# MCU.net
KiCad netlist of a schematic drawn in Altium Designer
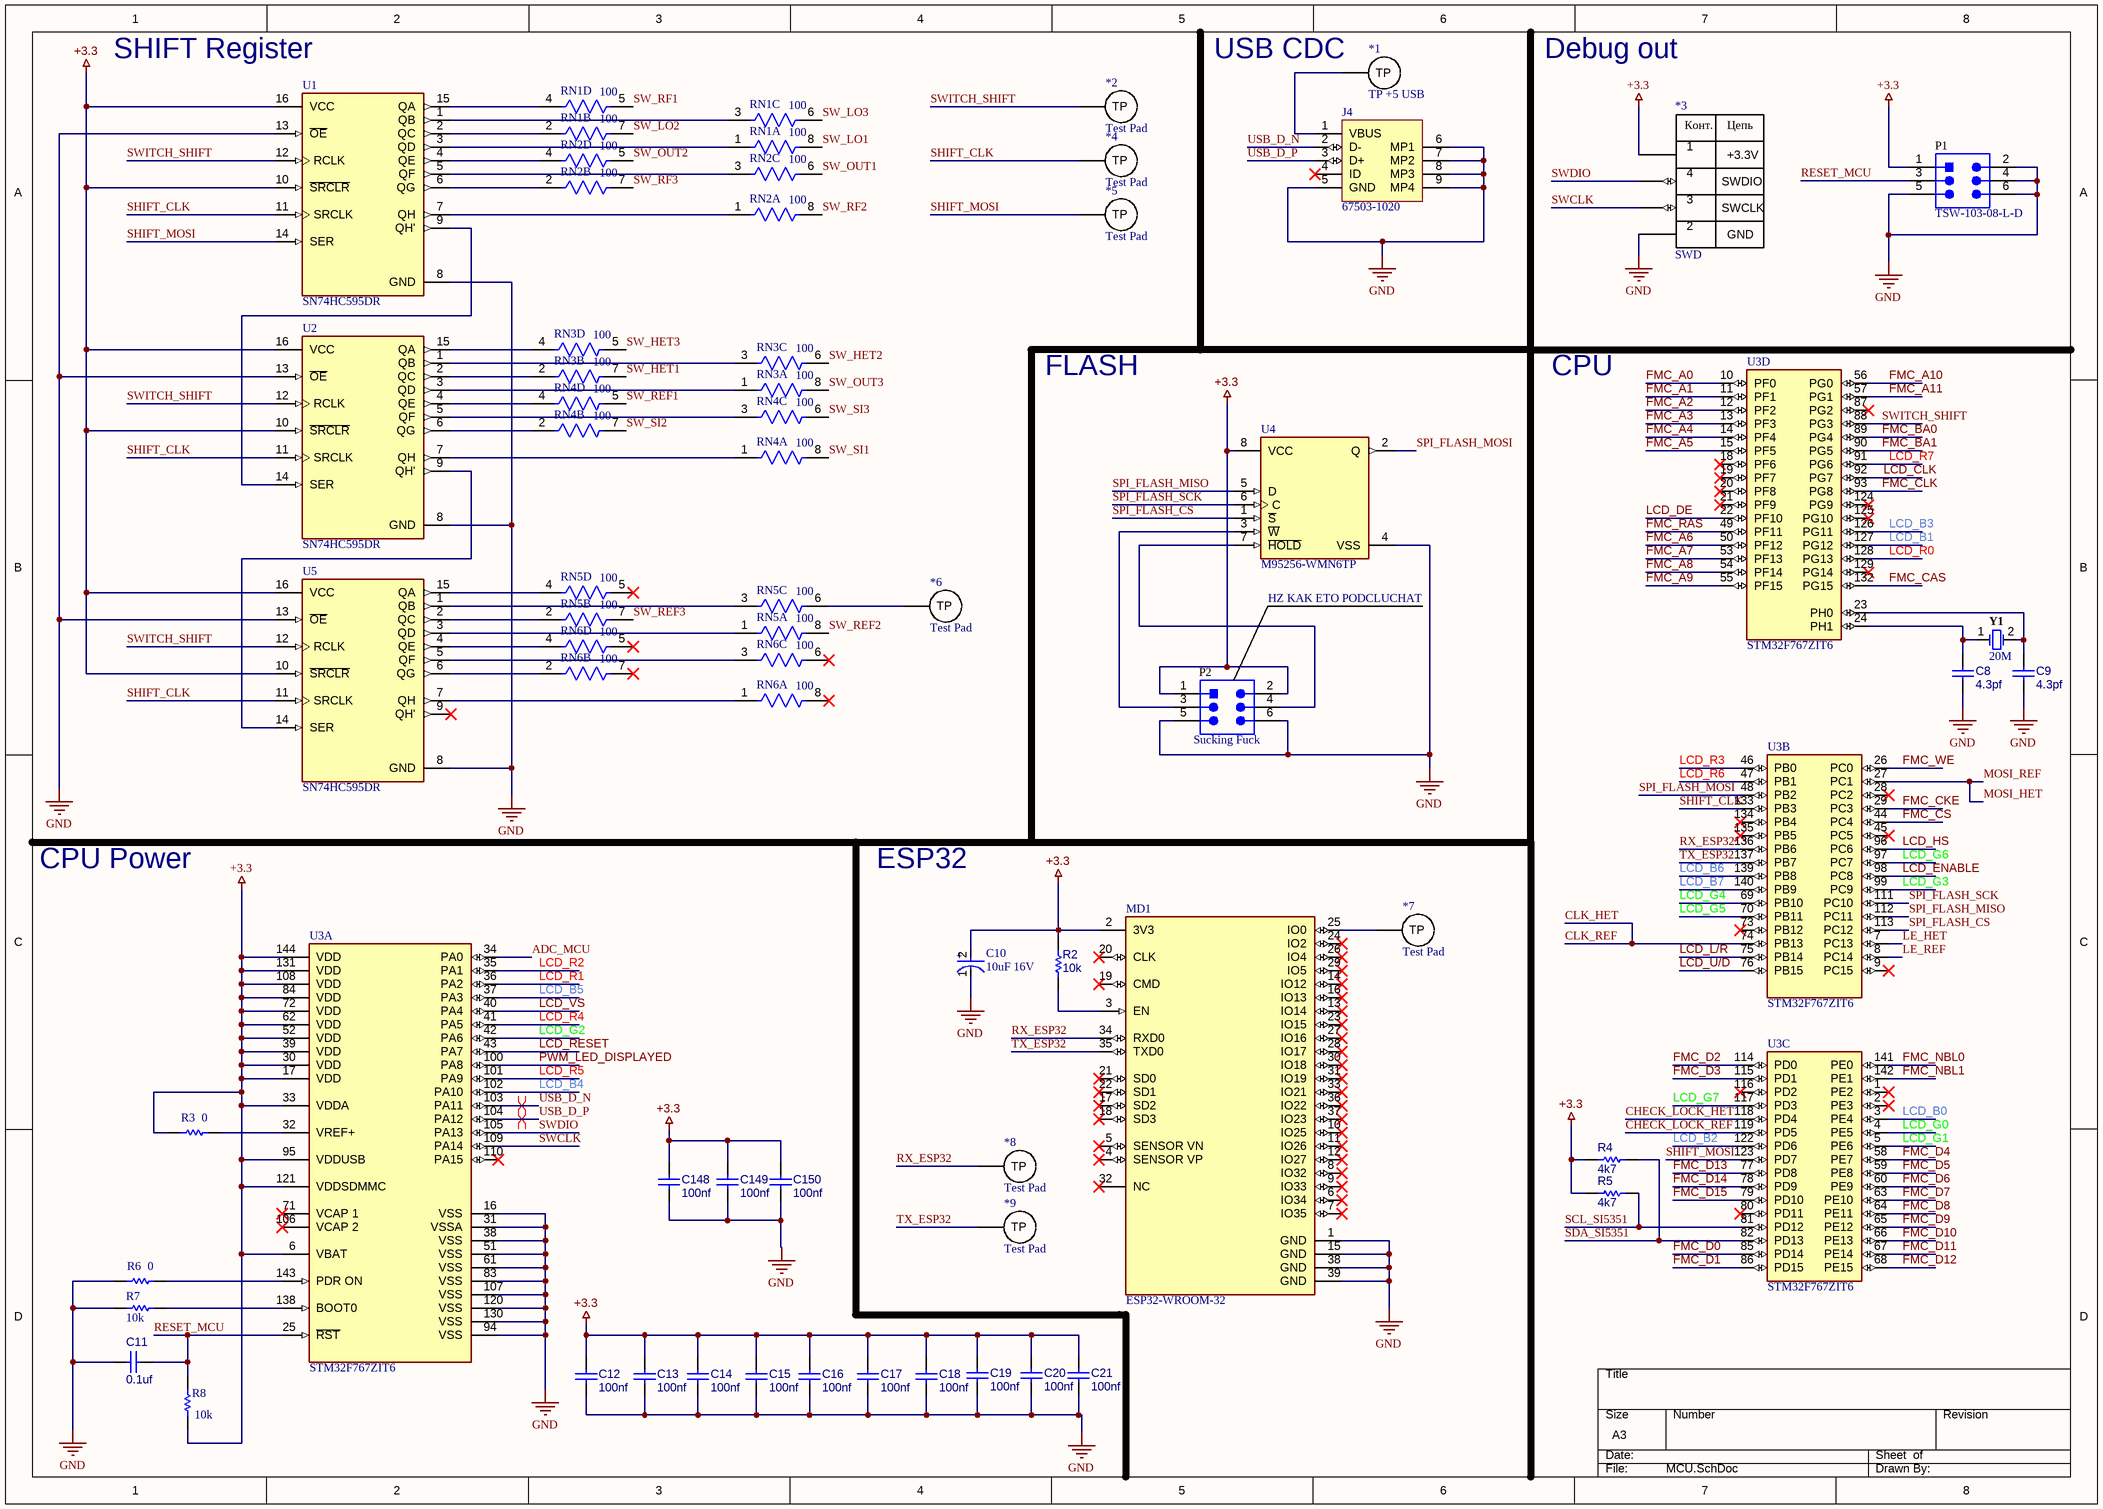
[diagram p0: MCU.SchDoc]

(export (version "E")
  (design (tool "Eeschema 10.0.6"))
  (components
    (comp (ref "*1")
      (value "TP +5 USB")
      (footprint "Test Pad")
      (libsource (lib "Test Pad") (part "Test Pad"))
    )
    (comp (ref "*2") (value "Test Pad") (footprint "Test Pad") (libsource (lib "Test Pad") (part "Test Pad")))
    (comp (ref "*3") (value "SWD") (footprint "PCBComponent_1") (libsource (lib "PAD") (part "SWD")))
    (comp (ref "*4") (value "Test Pad") (footprint "Test Pad") (libsource (lib "Test Pad") (part "Test Pad")))
    (comp (ref "*5") (value "Test Pad") (footprint "Test Pad") (libsource (lib "Test Pad") (part "Test Pad")))
    (comp (ref "*6") (value "Test Pad") (footprint "Test Pad") (libsource (lib "Test Pad") (part "Test Pad")))
    (comp (ref "*7") (value "Test Pad") (footprint "Test Pad") (libsource (lib "Test Pad") (part "Test Pad")))
    (comp (ref "*8") (value "Test Pad") (footprint "Test Pad") (libsource (lib "Test Pad") (part "Test Pad")))
    (comp (ref "*9") (value "Test Pad") (footprint "Test Pad") (libsource (lib "Test Pad") (part "Test Pad")))
    (comp (ref "C8")
      (value "4.3pf")
      (footprint "CAPC2013X70X45NL10T25")
      (fields (field (name "PART NUMBER") "GRM216R61E105KA12D") (field (name "MANUFACTURER") "Murata"))
      (libsource (lib "Altium Content Vault") (part "CAP"))
    )
    (comp (ref "C9")
      (value "4.3pf")
      (footprint "CAPC2013X70X45NL10T25")
      (fields (field (name "PART NUMBER") "GRM216R61E105KA12D") (field (name "MANUFACTURER") "Murata"))
      (libsource (lib "Altium Content Vault") (part "CAP"))
    )
    (comp (ref "C10")
      (value "10uF 16V")
      (footprint "FP-TAJA-MFG")
      (description "3.3uF 25V  ±20% 3.7Ω 1206  SMD Tantalum Capacitor")
      (fields (field (name "TOLERANCE") "20%"))
      (libsource (lib "Altium Content Vault") (part "203bc49f2ac43e59fd269a8c329ed05"))
    )
    (comp (ref "C11")
      (value "0.1uf")
      (footprint "CAPC2013X70X45NL10T25")
      (fields (field (name "PART NUMBER") "GRM216R61E105KA12D") (field (name "MANUFACTURER") "Murata"))
      (libsource (lib "Altium Content Vault") (part "CAP"))
    )
    (comp (ref "C12")
      (value "100nf")
      (footprint "CAPC2013X70X45NL10T25")
      (fields (field (name "PART NUMBER") "GRM216R61E105KA12D") (field (name "MANUFACTURER") "Murata"))
      (libsource (lib "Altium Content Vault") (part "CAP"))
    )
    (comp (ref "C13")
      (value "100nf")
      (footprint "CAPC2013X70X45NL10T25")
      (fields (field (name "PART NUMBER") "GRM216R61E105KA12D") (field (name "MANUFACTURER") "Murata"))
      (libsource (lib "Altium Content Vault") (part "CAP"))
    )
    (comp (ref "C14")
      (value "100nf")
      (footprint "CAPC2013X70X45NL10T25")
      (fields (field (name "PART NUMBER") "GRM216R61E105KA12D") (field (name "MANUFACTURER") "Murata"))
      (libsource (lib "Altium Content Vault") (part "CAP"))
    )
    (comp (ref "C15")
      (value "100nf")
      (footprint "CAPC2013X70X45NL10T25")
      (fields (field (name "PART NUMBER") "GRM216R61E105KA12D") (field (name "MANUFACTURER") "Murata"))
      (libsource (lib "Altium Content Vault") (part "CAP"))
    )
    (comp (ref "C16")
      (value "100nf")
      (footprint "CAPC2013X70X45NL10T25")
      (fields (field (name "PART NUMBER") "GRM216R61E105KA12D") (field (name "MANUFACTURER") "Murata"))
      (libsource (lib "Altium Content Vault") (part "CAP"))
    )
    (comp (ref "C17")
      (value "100nf")
      (footprint "CAPC2013X70X45NL10T25")
      (fields (field (name "PART NUMBER") "GRM216R61E105KA12D") (field (name "MANUFACTURER") "Murata"))
      (libsource (lib "Altium Content Vault") (part "CAP"))
    )
    (comp (ref "C18")
      (value "100nf")
      (footprint "CAPC2013X70X45NL10T25")
      (fields (field (name "PART NUMBER") "GRM216R61E105KA12D") (field (name "MANUFACTURER") "Murata"))
      (libsource (lib "Altium Content Vault") (part "CAP"))
    )
    (comp (ref "C19")
      (value "100nf")
      (footprint "CAPC2013X70X45NL10T25")
      (fields (field (name "PART NUMBER") "GRM216R61E105KA12D") (field (name "MANUFACTURER") "Murata"))
      (libsource (lib "Altium Content Vault") (part "CAP"))
    )
    (comp (ref "C20")
      (value "100nf")
      (footprint "CAPC2013X70X45NL10T25")
      (fields (field (name "PART NUMBER") "GRM216R61E105KA12D") (field (name "MANUFACTURER") "Murata"))
      (libsource (lib "Altium Content Vault") (part "CAP"))
    )
    (comp (ref "C21")
      (value "100nf")
      (footprint "CAPC2013X70X45NL10T25")
      (fields (field (name "PART NUMBER") "GRM216R61E105KA12D") (field (name "MANUFACTURER") "Murata"))
      (libsource (lib "Altium Content Vault") (part "CAP"))
    )
    (comp (ref "C148")
      (value "100nf")
      (footprint "CAPC2013X70X45NL10T25")
      (fields (field (name "PART NUMBER") "GRM216R61E105KA12D") (field (name "MANUFACTURER") "Murata"))
      (libsource (lib "Altium Content Vault") (part "CAP"))
    )
    (comp (ref "C149")
      (value "100nf")
      (footprint "CAPC2013X70X45NL10T25")
      (fields (field (name "PART NUMBER") "GRM216R61E105KA12D") (field (name "MANUFACTURER") "Murata"))
      (libsource (lib "Altium Content Vault") (part "CAP"))
    )
    (comp (ref "C150")
      (value "100nf")
      (footprint "CAPC2013X70X45NL10T25")
      (fields (field (name "PART NUMBER") "GRM216R61E105KA12D") (field (name "MANUFACTURER") "Murata"))
      (libsource (lib "Altium Content Vault") (part "CAP"))
    )
    (comp (ref "J4")
      (value "67503-1020")
      (footprint "MOLX-67503-1020_V")
      (description "USB, MINI, SMD, RA KME04-USBMU03A01")
      (fields (field (name "MANUFACTURER") "Molex"))
      (libsource (lib "Altium Content Vault") (part "MOLX-67503-1020"))
    )
    (comp (ref "MD1")
      (value "ESP32-WROOM-32")
      (footprint "FP-ESP32-WROOM-32-MFG")
      (description "RX TXRX MOD WIFI SURFACE MOUNT")
      (libsource (lib "Altium Content Vault") (part "ee866abf0b6c51247b7f5cdebf2f250"))
    )
    (comp (ref "P1")
      (value "TSW-103-08-L-D")
      (footprint "SMTC-TSW-103-08-L-D_V")
      (fields (field (name "MANUFACTURER") "Samtec"))
      (libsource (lib "Altium Content Vault") (part "CN-2P-M-R6"))
    )
    (comp (ref "P2")
      (value "Sucking Fuck")
      (footprint "SMTC-TSW-103-08-L-D_V")
      (fields (field (name "MANUFACTURER") "Samtec"))
      (libsource (lib "Altium Content Vault") (part "CN-2P-M-R6"))
    )
    (comp (ref "R2")
      (value "10k")
      (footprint "RESC2013X60X35ML10T20")
      (description "Chip Resistor, 1 KOhm, +/- 1%, 125 mW, -55 to 155 degC, 0805 (2012 Metric), RoHS, Tape and Reel")
      (fields (field (name "TOLERANCE") "1%") (field (name "MANUFACTURER") "Yageo"))
      (libsource (lib "Altium Content Vault") (part "RES-2"))
    )
    (comp (ref "R3")
      (value "0")
      (footprint "RESC2013X60X35ML10T20")
      (description "Chip Resistor, 1 KOhm, +/- 1%, 125 mW, -55 to 155 degC, 0805 (2012 Metric), RoHS, Tape and Reel")
      (fields (field (name "TOLERANCE") "1%") (field (name "MANUFACTURER") "Yageo"))
      (libsource (lib "Altium Content Vault") (part "RES-2"))
    )
    (comp (ref "R4")
      (value "4k7")
      (footprint "RESC2013X60X35ML10T20")
      (description "Chip Resistor, 1 KOhm, +/- 1%, 125 mW, -55 to 155 degC, 0805 (2012 Metric), RoHS, Tape and Reel")
      (fields (field (name "TOLERANCE") "1%") (field (name "MANUFACTURER") "Yageo"))
      (libsource (lib "Altium Content Vault") (part "RES-2"))
    )
    (comp (ref "R5")
      (value "4k7")
      (footprint "RESC2013X60X35ML10T20")
      (description "Chip Resistor, 1 KOhm, +/- 1%, 125 mW, -55 to 155 degC, 0805 (2012 Metric), RoHS, Tape and Reel")
      (fields (field (name "TOLERANCE") "1%") (field (name "MANUFACTURER") "Yageo"))
      (libsource (lib "Altium Content Vault") (part "RES-2"))
    )
    (comp (ref "R6")
      (value "0")
      (footprint "RESC2013X60X35ML10T20")
      (description "Chip Resistor, 1 KOhm, +/- 1%, 125 mW, -55 to 155 degC, 0805 (2012 Metric), RoHS, Tape and Reel")
      (fields (field (name "TOLERANCE") "1%") (field (name "MANUFACTURER") "Yageo"))
      (libsource (lib "Altium Content Vault") (part "RES-2"))
    )
    (comp (ref "R7")
      (value "10k")
      (footprint "RESC2013X60X35ML10T20")
      (description "Chip Resistor, 1 KOhm, +/- 1%, 125 mW, -55 to 155 degC, 0805 (2012 Metric), RoHS, Tape and Reel")
      (fields (field (name "TOLERANCE") "1%") (field (name "MANUFACTURER") "Yageo"))
      (libsource (lib "Altium Content Vault") (part "RES-2"))
    )
    (comp (ref "R8")
      (value "10k")
      (footprint "RESC2013X60X35ML10T20")
      (description "Chip Resistor, 1 KOhm, +/- 1%, 125 mW, -55 to 155 degC, 0805 (2012 Metric), RoHS, Tape and Reel")
      (fields (field (name "TOLERANCE") "1%") (field (name "MANUFACTURER") "Yageo"))
      (libsource (lib "Altium Content Vault") (part "RES-2"))
    )
    (comp (ref "RN1")
      (value "100")
      (footprint "FP-742C083-MFG")
      (description "RES ARRAY 4 RES 22 OHM 1206")
      (fields (field (name "TOLERANCE") "5%"))
      (libsource (lib "Altium Content Vault") (part "46c0e806a6f3a765a2d55930d12d044"))
    )
    (comp (ref "RN2")
      (value "100")
      (footprint "FP-742C083-MFG")
      (description "RES ARRAY 4 RES 22 OHM 1206")
      (fields (field (name "TOLERANCE") "5%"))
      (libsource (lib "Altium Content Vault") (part "46c0e806a6f3a765a2d55930d12d044"))
    )
    (comp (ref "RN3")
      (value "100")
      (footprint "FP-742C083-MFG")
      (description "RES ARRAY 4 RES 22 OHM 1206")
      (fields (field (name "TOLERANCE") "5%"))
      (libsource (lib "Altium Content Vault") (part "46c0e806a6f3a765a2d55930d12d044"))
    )
    (comp (ref "RN4")
      (value "100")
      (footprint "FP-742C083-MFG")
      (description "RES ARRAY 4 RES 22 OHM 1206")
      (fields (field (name "TOLERANCE") "5%"))
      (libsource (lib "Altium Content Vault") (part "46c0e806a6f3a765a2d55930d12d044"))
    )
    (comp (ref "RN5")
      (value "100")
      (footprint "FP-742C083-MFG")
      (description "RES ARRAY 4 RES 22 OHM 1206")
      (fields (field (name "TOLERANCE") "5%"))
      (libsource (lib "Altium Content Vault") (part "46c0e806a6f3a765a2d55930d12d044"))
    )
    (comp (ref "RN6")
      (value "100")
      (footprint "FP-742C083-MFG")
      (description "RES ARRAY 4 RES 22 OHM 1206")
      (fields (field (name "TOLERANCE") "5%"))
      (libsource (lib "Altium Content Vault") (part "46c0e806a6f3a765a2d55930d12d044"))
    )
    (comp (ref "U1")
      (value "SN74HC595DR")
      (footprint "FP-D0016A-MFG")
      (description "IC 8BIT SHIFT REG 3ST-OUT 16SOIC")
      (fields
        (field (name "OCTOPART") "https://octopart.com/sn74hc595dr-texas+instruments-500634")
        (field (name "MANUFACTURER") "Texas Instruments")
      )
      (libsource (lib "Altium Content Vault") (part "0ab4b57b7d735ad423582b9991672f6"))
    )
    (comp (ref "U2")
      (value "SN74HC595DR")
      (footprint "FP-D0016A-MFG")
      (description "IC 8BIT SHIFT REG 3ST-OUT 16SOIC")
      (fields
        (field (name "OCTOPART") "https://octopart.com/sn74hc595dr-texas+instruments-500634")
        (field (name "MANUFACTURER") "Texas Instruments")
      )
      (libsource (lib "Altium Content Vault") (part "0ab4b57b7d735ad423582b9991672f6"))
    )
    (comp (ref "U3")
      (value "STM32F767ZIT6")
      (footprint "FP-LQFP144-1A-MFG")
      (description "IC MCU 32BIT 2MB FLASH 144LQFP")
      (fields
        (field (name "OCTOPART") "https://octopart.com/stm32f767zit6-stmicroelectronics-70527068")
        (field (name "MANUFACTURER") "STMicroelectronics")
      )
      (libsource (lib "Altium Content Vault") (part "5045e889cff10565096e715f5715cbd"))
    )
    (comp (ref "U4")
      (value "M95256-WMN6TP")
      (footprint "FP-SO8N-SO-A-MFG")
      (description "IC EEPROM 256K SPI 20MHZ 8SO")
      (fields
        (field (name "MANUFACTURER") "STMicroelectronics")
        (field (name "OCTOPART") "https://octopart.com/m95256-wmn6tp-stmicroelectronics-842801")
      )
      (libsource (lib "Altium Content Vault") (part "459af80fb051d719541373de607d02b"))
    )
    (comp (ref "U5")
      (value "SN74HC595DR")
      (footprint "FP-D0016A-MFG")
      (description "IC 8BIT SHIFT REG 3ST-OUT 16SOIC")
      (fields
        (field (name "OCTOPART") "https://octopart.com/sn74hc595dr-texas+instruments-500634")
        (field (name "MANUFACTURER") "Texas Instruments")
      )
      (libsource (lib "Altium Content Vault") (part "0ab4b57b7d735ad423582b9991672f6"))
    )
    (comp (ref "Y1")
      (value "20M")
      (footprint "FOX-FOXSLF-2_V")
      (description "Resistance Weld Thru-Hole Crystal, 12 MHz, +/-30 ppm, -20 to 70 degC, 2-Pin THD, RoHS, Bulk")
      (libsource (lib "Altium Content Vault") (part "XTAL-1-2-2"))
    )
  )
  (nets
    (net (code "1") (name "+3.3") (class "Default")
      (node (ref "*3") (pin "1") (pinfunction "+3.3V_1") (pintype "power_in"))
      (node (ref "C10") (pin "2") (pinfunction "A_2") (pintype "passive"))
      (node (ref "C12") (pin "2") (pinfunction "2_2") (pintype "passive"))
      (node (ref "C13") (pin "2") (pinfunction "2_2") (pintype "passive"))
      (node (ref "C14") (pin "2") (pinfunction "2_2") (pintype "passive"))
      (node (ref "C148") (pin "2") (pinfunction "2_2") (pintype "passive"))
      (node (ref "C149") (pin "2") (pinfunction "2_2") (pintype "passive"))
      (node (ref "C15") (pin "2") (pinfunction "2_2") (pintype "passive"))
      (node (ref "C150") (pin "2") (pinfunction "2_2") (pintype "passive"))
      (node (ref "C16") (pin "2") (pinfunction "2_2") (pintype "passive"))
      (node (ref "C17") (pin "2") (pinfunction "2_2") (pintype "passive"))
      (node (ref "C18") (pin "2") (pinfunction "2_2") (pintype "passive"))
      (node (ref "C19") (pin "2") (pinfunction "2_2") (pintype "passive"))
      (node (ref "C20") (pin "2") (pinfunction "2_2") (pintype "passive"))
      (node (ref "C21") (pin "2") (pinfunction "2_2") (pintype "passive"))
      (node (ref "MD1") (pin "2") (pinfunction "3V3_2") (pintype "power_in"))
      (node (ref "P1") (pin "1") (pinfunction "1_1") (pintype "passive"))
      (node (ref "P2") (pin "1") (pinfunction "1_1") (pintype "passive"))
      (node (ref "P2") (pin "2") (pinfunction "2_2") (pintype "passive"))
      (node (ref "R2") (pin "2") (pinfunction "2_2") (pintype "passive"))
      (node (ref "R3") (pin "2") (pinfunction "2_2") (pintype "passive"))
      (node (ref "R4") (pin "2") (pinfunction "2_2") (pintype "passive"))
      (node (ref "R5") (pin "2") (pinfunction "2_2") (pintype "passive"))
      (node (ref "R8") (pin "1") (pinfunction "1_1") (pintype "passive"))
      (node (ref "U1") (pin "10") (pinfunction "~{SRCLR}_10") (pintype "input"))
      (node (ref "U1") (pin "16") (pinfunction "VCC_16") (pintype "power_in"))
      (node (ref "U2") (pin "10") (pinfunction "~{SRCLR}_10") (pintype "input"))
      (node (ref "U2") (pin "16") (pinfunction "VCC_16") (pintype "power_in"))
      (node (ref "U3") (pin "108") (pinfunction "VDD_108") (pintype "power_in"))
      (node (ref "U3") (pin "121") (pinfunction "VDDSDMMC_121") (pintype "power_in"))
      (node (ref "U3") (pin "131") (pinfunction "VDD_131") (pintype "power_in"))
      (node (ref "U3") (pin "144") (pinfunction "VDD_144") (pintype "power_in"))
      (node (ref "U3") (pin "17") (pinfunction "VDD_17") (pintype "power_in"))
      (node (ref "U3") (pin "30") (pinfunction "VDD_30") (pintype "power_in"))
      (node (ref "U3") (pin "33") (pinfunction "VDDA_33") (pintype "power_in"))
      (node (ref "U3") (pin "39") (pinfunction "VDD_39") (pintype "power_in"))
      (node (ref "U3") (pin "52") (pinfunction "VDD_52") (pintype "power_in"))
      (node (ref "U3") (pin "6") (pinfunction "VBAT_6") (pintype "power_in"))
      (node (ref "U3") (pin "62") (pinfunction "VDD_62") (pintype "power_in"))
      (node (ref "U3") (pin "72") (pinfunction "VDD_72") (pintype "power_in"))
      (node (ref "U3") (pin "84") (pinfunction "VDD_84") (pintype "power_in"))
      (node (ref "U3") (pin "95") (pinfunction "VDDUSB_95") (pintype "power_in"))
      (node (ref "U4") (pin "8") (pinfunction "VCC_8") (pintype "power_in"))
      (node (ref "U5") (pin "10") (pinfunction "~{SRCLR}_10") (pintype "input"))
      (node (ref "U5") (pin "16") (pinfunction "VCC_16") (pintype "power_in"))
    )
    (net (code "2") (name "/ADC_MCU") (class "Default")
      (node (ref "U3") (pin "34") (pinfunction "PA0_34") (pintype "bidirectional"))
    )
    (net (code "3") (name "/CHECK_LOCK_HET") (class "Default")
      (node (ref "U3") (pin "118") (pinfunction "PD4_118") (pintype "bidirectional"))
    )
    (net (code "4") (name "/CHECK_LOCK_REF") (class "Default")
      (node (ref "U3") (pin "119") (pinfunction "PD5_119") (pintype "bidirectional"))
    )
    (net (code "5") (name "/CLK_HET") (class "Default")
      (node (ref "U3") (pin "74") (pinfunction "PB13_74") (pintype "bidirectional"))
    )
    (net (code "6") (name "/FMC_A0") (class "Default")
      (node (ref "U3") (pin "10") (pinfunction "PF0_10") (pintype "bidirectional"))
    )
    (net (code "7") (name "/FMC_A1") (class "Default")
      (node (ref "U3") (pin "11") (pinfunction "PF1_11") (pintype "bidirectional"))
    )
    (net (code "8") (name "/FMC_A2") (class "Default")
      (node (ref "U3") (pin "12") (pinfunction "PF2_12") (pintype "bidirectional"))
    )
    (net (code "9") (name "/FMC_A3") (class "Default")
      (node (ref "U3") (pin "13") (pinfunction "PF3_13") (pintype "bidirectional"))
    )
    (net (code "10") (name "/FMC_A4") (class "Default")
      (node (ref "U3") (pin "14") (pinfunction "PF4_14") (pintype "bidirectional"))
    )
    (net (code "11") (name "/FMC_A5") (class "Default")
      (node (ref "U3") (pin "15") (pinfunction "PF5_15") (pintype "bidirectional"))
    )
    (net (code "12") (name "/FMC_A6") (class "Default")
      (node (ref "U3") (pin "50") (pinfunction "PF12_50") (pintype "bidirectional"))
    )
    (net (code "13") (name "/FMC_A7") (class "Default")
      (node (ref "U3") (pin "53") (pinfunction "PF13_53") (pintype "bidirectional"))
    )
    (net (code "14") (name "/FMC_A8") (class "Default")
      (node (ref "U3") (pin "54") (pinfunction "PF14_54") (pintype "bidirectional"))
    )
    (net (code "15") (name "/FMC_A9") (class "Default")
      (node (ref "U3") (pin "55") (pinfunction "PF15_55") (pintype "bidirectional"))
    )
    (net (code "16") (name "/FMC_A10") (class "Default")
      (node (ref "U3") (pin "56") (pinfunction "PG0_56") (pintype "bidirectional"))
    )
    (net (code "17") (name "/FMC_A11") (class "Default")
      (node (ref "U3") (pin "57") (pinfunction "PG1_57") (pintype "bidirectional"))
    )
    (net (code "18") (name "/FMC_BA0") (class "Default")
      (node (ref "U3") (pin "89") (pinfunction "PG4_89") (pintype "bidirectional"))
    )
    (net (code "19") (name "/FMC_BA1") (class "Default")
      (node (ref "U3") (pin "90") (pinfunction "PG5_90") (pintype "bidirectional"))
    )
    (net (code "20") (name "/FMC_CAS") (class "Default")
      (node (ref "U3") (pin "132") (pinfunction "PG15_132") (pintype "bidirectional"))
    )
    (net (code "21") (name "/FMC_CKE") (class "Default")
      (node (ref "U3") (pin "29") (pinfunction "PC3_29") (pintype "bidirectional"))
    )
    (net (code "22") (name "/FMC_CLK") (class "Default")
      (node (ref "U3") (pin "93") (pinfunction "PG8_93") (pintype "bidirectional"))
    )
    (net (code "23") (name "/FMC_CS") (class "Default")
      (node (ref "U3") (pin "44") (pinfunction "PC4_44") (pintype "bidirectional"))
    )
    (net (code "24") (name "/FMC_D0") (class "Default")
      (node (ref "U3") (pin "85") (pinfunction "PD14_85") (pintype "bidirectional"))
    )
    (net (code "25") (name "/FMC_D1") (class "Default")
      (node (ref "U3") (pin "86") (pinfunction "PD15_86") (pintype "bidirectional"))
    )
    (net (code "26") (name "/FMC_D2") (class "Default")
      (node (ref "U3") (pin "114") (pinfunction "PD0_114") (pintype "bidirectional"))
    )
    (net (code "27") (name "/FMC_D3") (class "Default")
      (node (ref "U3") (pin "115") (pinfunction "PD1_115") (pintype "bidirectional"))
    )
    (net (code "28") (name "/FMC_D4") (class "Default")
      (node (ref "U3") (pin "58") (pinfunction "PE7_58") (pintype "bidirectional"))
    )
    (net (code "29") (name "/FMC_D5") (class "Default")
      (node (ref "U3") (pin "59") (pinfunction "PE8_59") (pintype "bidirectional"))
    )
    (net (code "30") (name "/FMC_D6") (class "Default")
      (node (ref "U3") (pin "60") (pinfunction "PE9_60") (pintype "bidirectional"))
    )
    (net (code "31") (name "/FMC_D7") (class "Default")
      (node (ref "U3") (pin "63") (pinfunction "PE10_63") (pintype "bidirectional"))
    )
    (net (code "32") (name "/FMC_D8") (class "Default")
      (node (ref "U3") (pin "64") (pinfunction "PE11_64") (pintype "bidirectional"))
    )
    (net (code "33") (name "/FMC_D9") (class "Default")
      (node (ref "U3") (pin "65") (pinfunction "PE12_65") (pintype "bidirectional"))
    )
    (net (code "34") (name "/FMC_D10") (class "Default")
      (node (ref "U3") (pin "66") (pinfunction "PE13_66") (pintype "bidirectional"))
    )
    (net (code "35") (name "/FMC_D11") (class "Default")
      (node (ref "U3") (pin "67") (pinfunction "PE14_67") (pintype "bidirectional"))
    )
    (net (code "36") (name "/FMC_D12") (class "Default")
      (node (ref "U3") (pin "68") (pinfunction "PE15_68") (pintype "bidirectional"))
    )
    (net (code "37") (name "/FMC_D13") (class "Default")
      (node (ref "U3") (pin "77") (pinfunction "PD8_77") (pintype "bidirectional"))
    )
    (net (code "38") (name "/FMC_D14") (class "Default")
      (node (ref "U3") (pin "78") (pinfunction "PD9_78") (pintype "bidirectional"))
    )
    (net (code "39") (name "/FMC_D15") (class "Default")
      (node (ref "U3") (pin "79") (pinfunction "PD10_79") (pintype "bidirectional"))
    )
    (net (code "40") (name "/FMC_NBL0") (class "Default")
      (node (ref "U3") (pin "141") (pinfunction "PE0_141") (pintype "bidirectional"))
    )
    (net (code "41") (name "/FMC_NBL1") (class "Default")
      (node (ref "U3") (pin "142") (pinfunction "PE1_142") (pintype "bidirectional"))
    )
    (net (code "42") (name "/FMC_RAS") (class "Default")
      (node (ref "U3") (pin "49") (pinfunction "PF11_49") (pintype "bidirectional"))
    )
    (net (code "43") (name "/FMC_WE") (class "Default")
      (node (ref "U3") (pin "26") (pinfunction "PC0_26") (pintype "bidirectional"))
    )
    (net (code "44") (name "/LCD_B0") (class "Default")
      (node (ref "U3") (pin "3") (pinfunction "PE4_3") (pintype "bidirectional"))
    )
    (net (code "45") (name "/LCD_B1") (class "Default")
      (node (ref "U3") (pin "127") (pinfunction "PG12_127") (pintype "bidirectional"))
    )
    (net (code "46") (name "/LCD_B2") (class "Default")
      (node (ref "U3") (pin "122") (pinfunction "PD6_122") (pintype "bidirectional"))
    )
    (net (code "47") (name "/LCD_B3") (class "Default")
      (node (ref "U3") (pin "126") (pinfunction "PG11_126") (pintype "bidirectional"))
    )
    (net (code "48") (name "/LCD_B4") (class "Default")
      (node (ref "U3") (pin "102") (pinfunction "PA10_102") (pintype "bidirectional"))
    )
    (net (code "49") (name "/LCD_B5") (class "Default")
      (node (ref "U3") (pin "37") (pinfunction "PA3_37") (pintype "bidirectional"))
    )
    (net (code "50") (name "/LCD_B6") (class "Default")
      (node (ref "U3") (pin "139") (pinfunction "PB8_139") (pintype "bidirectional"))
    )
    (net (code "51") (name "/LCD_B7") (class "Default")
      (node (ref "U3") (pin "140") (pinfunction "PB9_140") (pintype "bidirectional"))
    )
    (net (code "52") (name "/LCD_CLK") (class "Default")
      (node (ref "U3") (pin "92") (pinfunction "PG7_92") (pintype "bidirectional"))
    )
    (net (code "53") (name "/LCD_DE") (class "Default")
      (node (ref "U3") (pin "22") (pinfunction "PF10_22") (pintype "bidirectional"))
    )
    (net (code "54") (name "/LCD_ENABLE") (class "Default")
      (node (ref "U3") (pin "98") (pinfunction "PC8_98") (pintype "bidirectional"))
    )
    (net (code "55") (name "/LCD_G0") (class "Default")
      (node (ref "U3") (pin "4") (pinfunction "PE5_4") (pintype "bidirectional"))
    )
    (net (code "56") (name "/LCD_G1") (class "Default")
      (node (ref "U3") (pin "5") (pinfunction "PE6_5") (pintype "bidirectional"))
    )
    (net (code "57") (name "/LCD_G2") (class "Default")
      (node (ref "U3") (pin "42") (pinfunction "PA6_42") (pintype "bidirectional"))
    )
    (net (code "58") (name "/LCD_G3") (class "Default")
      (node (ref "U3") (pin "99") (pinfunction "PC9_99") (pintype "bidirectional"))
    )
    (net (code "59") (name "/LCD_G4") (class "Default")
      (node (ref "U3") (pin "69") (pinfunction "PB10_69") (pintype "bidirectional"))
    )
    (net (code "60") (name "/LCD_G5") (class "Default")
      (node (ref "U3") (pin "70") (pinfunction "PB11_70") (pintype "bidirectional"))
    )
    (net (code "61") (name "/LCD_G6") (class "Default")
      (node (ref "U3") (pin "97") (pinfunction "PC7_97") (pintype "bidirectional"))
    )
    (net (code "62") (name "/LCD_G7") (class "Default")
      (node (ref "U3") (pin "117") (pinfunction "PD3_117") (pintype "bidirectional"))
    )
    (net (code "63") (name "/LCD_HS") (class "Default")
      (node (ref "U3") (pin "96") (pinfunction "PC6_96") (pintype "bidirectional"))
    )
    (net (code "64") (name "/LCD_L{slash}R") (class "Default")
      (node (ref "U3") (pin "75") (pinfunction "PB14_75") (pintype "bidirectional"))
    )
    (net (code "65") (name "/LCD_R0") (class "Default")
      (node (ref "U3") (pin "128") (pinfunction "PG13_128") (pintype "bidirectional"))
    )
    (net (code "66") (name "/LCD_R1") (class "Default")
      (node (ref "U3") (pin "36") (pinfunction "PA2_36") (pintype "bidirectional"))
    )
    (net (code "67") (name "/LCD_R2") (class "Default")
      (node (ref "U3") (pin "35") (pinfunction "PA1_35") (pintype "bidirectional"))
    )
    (net (code "68") (name "/LCD_R3") (class "Default")
      (node (ref "U3") (pin "46") (pinfunction "PB0_46") (pintype "bidirectional"))
    )
    (net (code "69") (name "/LCD_R4") (class "Default")
      (node (ref "U3") (pin "41") (pinfunction "PA5_41") (pintype "bidirectional"))
    )
    (net (code "70") (name "/LCD_R5") (class "Default")
      (node (ref "U3") (pin "101") (pinfunction "PA9_101") (pintype "bidirectional"))
    )
    (net (code "71") (name "/LCD_R6") (class "Default")
      (node (ref "U3") (pin "47") (pinfunction "PB1_47") (pintype "bidirectional"))
    )
    (net (code "72") (name "/LCD_R7") (class "Default")
      (node (ref "U3") (pin "91") (pinfunction "PG6_91") (pintype "bidirectional"))
    )
    (net (code "73") (name "/LCD_RESET") (class "Default")
      (node (ref "U3") (pin "43") (pinfunction "PA7_43") (pintype "bidirectional"))
    )
    (net (code "74") (name "/LCD_U{slash}D") (class "Default")
      (node (ref "U3") (pin "76") (pinfunction "PB15_76") (pintype "bidirectional"))
    )
    (net (code "75") (name "/LCD_VS") (class "Default")
      (node (ref "U3") (pin "40") (pinfunction "PA4_40") (pintype "bidirectional"))
    )
    (net (code "76") (name "/LE_HET") (class "Default")
      (node (ref "U3") (pin "7") (pinfunction "PC13_7") (pintype "bidirectional"))
    )
    (net (code "77") (name "/LE_REF") (class "Default")
      (node (ref "U3") (pin "8") (pinfunction "PC14_8") (pintype "bidirectional"))
    )
    (net (code "78") (name "/MOSI_HET") (class "Default")
      (node (ref "U3") (pin "27") (pinfunction "PC1_27") (pintype "bidirectional"))
    )
    (net (code "79") (name "/PWM_LED_DISPLAYED") (class "Default")
      (node (ref "U3") (pin "100") (pinfunction "PA8_100") (pintype "bidirectional"))
    )
    (net (code "80") (name "/RESET_MCU") (class "Default")
      (node (ref "C11") (pin "1") (pinfunction "1_1") (pintype "passive"))
      (node (ref "P1") (pin "3") (pinfunction "3_3") (pintype "passive"))
      (node (ref "R8") (pin "2") (pinfunction "2_2") (pintype "passive"))
      (node (ref "U3") (pin "25") (pinfunction "~{RST}_25") (pintype "input"))
    )
    (net (code "81") (name "/RX_ESP32") (class "Default")
      (node (ref "*8") (pin "1") (pinfunction "TP_1") (pintype "passive"))
      (node (ref "MD1") (pin "34") (pinfunction "RXD0_34") (pintype "bidirectional"))
      (node (ref "U3") (pin "136") (pinfunction "PB6_136") (pintype "bidirectional"))
    )
    (net (code "82") (name "/SCL_SI5351") (class "Default")
      (node (ref "R5") (pin "1") (pinfunction "1_1") (pintype "passive"))
      (node (ref "U3") (pin "81") (pinfunction "PD12_81") (pintype "bidirectional"))
    )
    (net (code "83") (name "/SDA_SI5351") (class "Default")
      (node (ref "R4") (pin "1") (pinfunction "1_1") (pintype "passive"))
      (node (ref "U3") (pin "82") (pinfunction "PD13_82") (pintype "bidirectional"))
    )
    (net (code "84") (name "/SHIFT_CLK") (class "Default")
      (node (ref "*4") (pin "1") (pinfunction "TP_1") (pintype "passive"))
      (node (ref "U1") (pin "11") (pinfunction "SRCLK_11") (pintype "input"))
      (node (ref "U2") (pin "11") (pinfunction "SRCLK_11") (pintype "input"))
      (node (ref "U3") (pin "133") (pinfunction "PB3_133") (pintype "bidirectional"))
      (node (ref "U5") (pin "11") (pinfunction "SRCLK_11") (pintype "input"))
    )
    (net (code "85") (name "/SHIFT_MOSI") (class "Default")
      (node (ref "*5") (pin "1") (pinfunction "TP_1") (pintype "passive"))
      (node (ref "U1") (pin "14") (pinfunction "SER_14") (pintype "input"))
      (node (ref "U3") (pin "123") (pinfunction "PD7_123") (pintype "bidirectional"))
    )
    (net (code "86") (name "/SPI_FLASH_CS") (class "Default")
      (node (ref "U3") (pin "113") (pinfunction "PC12_113") (pintype "bidirectional"))
      (node (ref "U4") (pin "1") (pinfunction "~{S}_1") (pintype "input"))
    )
    (net (code "87") (name "/SPI_FLASH_MISO") (class "Default")
      (node (ref "U3") (pin "112") (pinfunction "PC11_112") (pintype "bidirectional"))
      (node (ref "U4") (pin "5") (pinfunction "D_5") (pintype "input"))
    )
    (net (code "88") (name "/SPI_FLASH_MOSI") (class "Default")
      (node (ref "U3") (pin "48") (pinfunction "PB2_48") (pintype "bidirectional"))
      (node (ref "U4") (pin "2") (pinfunction "Q_2") (pintype "output"))
    )
    (net (code "89") (name "/SPI_FLASH_SCK") (class "Default")
      (node (ref "U3") (pin "111") (pinfunction "PC10_111") (pintype "bidirectional"))
      (node (ref "U4") (pin "6") (pinfunction "C_6") (pintype "input"))
    )
    (net (code "90") (name "/SWCLK") (class "Default")
      (node (ref "*3") (pin "3") (pinfunction "SWCLK_3") (pintype "bidirectional"))
      (node (ref "U3") (pin "109") (pinfunction "PA14_109") (pintype "bidirectional"))
    )
    (net (code "91") (name "/SWDIO") (class "Default")
      (node (ref "*3") (pin "4") (pinfunction "SWDIO_4") (pintype "bidirectional"))
      (node (ref "U3") (pin "105") (pinfunction "PA13_105") (pintype "bidirectional"))
    )
    (net (code "92") (name "/SWITCH_SHIFT") (class "Default")
      (node (ref "*2") (pin "1") (pinfunction "TP_1") (pintype "passive"))
      (node (ref "U1") (pin "12") (pinfunction "RCLK_12") (pintype "input"))
      (node (ref "U2") (pin "12") (pinfunction "RCLK_12") (pintype "input"))
      (node (ref "U3") (pin "88") (pinfunction "PG3_88") (pintype "bidirectional"))
      (node (ref "U5") (pin "12") (pinfunction "RCLK_12") (pintype "input"))
    )
    (net (code "93") (name "/SW_HET1") (class "Default")
      (node (ref "RN3") (pin "7") (pinfunction "7_7") (pintype "passive"))
    )
    (net (code "94") (name "/SW_HET2") (class "Default")
      (node (ref "RN3") (pin "6") (pinfunction "6_6") (pintype "passive"))
    )
    (net (code "95") (name "/SW_HET3") (class "Default")
      (node (ref "RN3") (pin "5") (pinfunction "5_5") (pintype "passive"))
    )
    (net (code "96") (name "/SW_LO1") (class "Default")
      (node (ref "RN1") (pin "8") (pinfunction "8_8") (pintype "passive"))
    )
    (net (code "97") (name "/SW_LO2") (class "Default")
      (node (ref "RN1") (pin "7") (pinfunction "7_7") (pintype "passive"))
    )
    (net (code "98") (name "/SW_LO3") (class "Default")
      (node (ref "RN1") (pin "6") (pinfunction "6_6") (pintype "passive"))
    )
    (net (code "99") (name "/SW_OUT1") (class "Default")
      (node (ref "RN2") (pin "6") (pinfunction "6_6") (pintype "passive"))
    )
    (net (code "100") (name "/SW_OUT2") (class "Default")
      (node (ref "RN2") (pin "5") (pinfunction "5_5") (pintype "passive"))
    )
    (net (code "101") (name "/SW_OUT3") (class "Default")
      (node (ref "RN3") (pin "8") (pinfunction "8_8") (pintype "passive"))
    )
    (net (code "102") (name "/SW_REF1") (class "Default")
      (node (ref "RN4") (pin "5") (pinfunction "5_5") (pintype "passive"))
    )
    (net (code "103") (name "/SW_REF2") (class "Default")
      (node (ref "RN5") (pin "8") (pinfunction "8_8") (pintype "passive"))
    )
    (net (code "104") (name "/SW_REF3") (class "Default")
      (node (ref "RN5") (pin "7") (pinfunction "7_7") (pintype "passive"))
    )
    (net (code "105") (name "/SW_RF1") (class "Default")
      (node (ref "RN1") (pin "5") (pinfunction "5_5") (pintype "passive"))
    )
    (net (code "106") (name "/SW_RF2") (class "Default")
      (node (ref "RN2") (pin "8") (pinfunction "8_8") (pintype "passive"))
    )
    (net (code "107") (name "/SW_RF3") (class "Default")
      (node (ref "RN2") (pin "7") (pinfunction "7_7") (pintype "passive"))
    )
    (net (code "108") (name "/SW_SI1") (class "Default")
      (node (ref "RN4") (pin "8") (pinfunction "8_8") (pintype "passive"))
    )
    (net (code "109") (name "/SW_SI2") (class "Default")
      (node (ref "RN4") (pin "7") (pinfunction "7_7") (pintype "passive"))
    )
    (net (code "110") (name "/SW_SI3") (class "Default")
      (node (ref "RN4") (pin "6") (pinfunction "6_6") (pintype "passive"))
    )
    (net (code "111") (name "/TX_ESP32") (class "Default")
      (node (ref "*9") (pin "1") (pinfunction "TP_1") (pintype "passive"))
      (node (ref "MD1") (pin "35") (pinfunction "TXD0_35") (pintype "bidirectional"))
      (node (ref "U3") (pin "137") (pinfunction "PB7_137") (pintype "bidirectional"))
    )
    (net (code "112") (name "/USB_D_N") (class "Default")
      (node (ref "J4") (pin "2") (pinfunction "D-_2") (pintype "bidirectional"))
      (node (ref "U3") (pin "103") (pinfunction "PA11_103") (pintype "bidirectional"))
    )
    (net (code "113") (name "/USB_D_P") (class "Default")
      (node (ref "J4") (pin "3") (pinfunction "D+_3") (pintype "bidirectional"))
      (node (ref "U3") (pin "104") (pinfunction "PA12_104") (pintype "bidirectional"))
    )
    (net (code "114") (name "GND") (class "Default")
      (node (ref "*3") (pin "2") (pinfunction "GND_2") (pintype "power_in"))
      (node (ref "C10") (pin "1") (pinfunction "C_1") (pintype "passive"))
      (node (ref "C11") (pin "2") (pinfunction "2_2") (pintype "passive"))
      (node (ref "C12") (pin "1") (pinfunction "1_1") (pintype "passive"))
      (node (ref "C13") (pin "1") (pinfunction "1_1") (pintype "passive"))
      (node (ref "C14") (pin "1") (pinfunction "1_1") (pintype "passive"))
      (node (ref "C148") (pin "1") (pinfunction "1_1") (pintype "passive"))
      (node (ref "C149") (pin "1") (pinfunction "1_1") (pintype "passive"))
      (node (ref "C15") (pin "1") (pinfunction "1_1") (pintype "passive"))
      (node (ref "C150") (pin "1") (pinfunction "1_1") (pintype "passive"))
      (node (ref "C16") (pin "1") (pinfunction "1_1") (pintype "passive"))
      (node (ref "C17") (pin "1") (pinfunction "1_1") (pintype "passive"))
      (node (ref "C18") (pin "1") (pinfunction "1_1") (pintype "passive"))
      (node (ref "C19") (pin "1") (pinfunction "1_1") (pintype "passive"))
      (node (ref "C20") (pin "1") (pinfunction "1_1") (pintype "passive"))
      (node (ref "C21") (pin "1") (pinfunction "1_1") (pintype "passive"))
      (node (ref "C8") (pin "2") (pinfunction "2_2") (pintype "passive"))
      (node (ref "C9") (pin "2") (pinfunction "2_2") (pintype "passive"))
      (node (ref "J4") (pin "5") (pinfunction "GND_5") (pintype "power_in"))
      (node (ref "J4") (pin "6") (pinfunction "MP1_6") (pintype "passive"))
      (node (ref "J4") (pin "7") (pinfunction "MP2_7") (pintype "passive"))
      (node (ref "J4") (pin "8") (pinfunction "MP3_8") (pintype "passive"))
      (node (ref "J4") (pin "9") (pinfunction "MP4_9") (pintype "passive"))
      (node (ref "MD1") (pin "1") (pinfunction "GND_1") (pintype "power_in"))
      (node (ref "MD1") (pin "15") (pinfunction "GND_15") (pintype "power_in"))
      (node (ref "MD1") (pin "38") (pinfunction "GND_38") (pintype "power_in"))
      (node (ref "MD1") (pin "39") (pinfunction "GND_39") (pintype "power_in"))
      (node (ref "P1") (pin "2") (pinfunction "2_2") (pintype "passive"))
      (node (ref "P1") (pin "4") (pinfunction "4_4") (pintype "passive"))
      (node (ref "P1") (pin "5") (pinfunction "5_5") (pintype "passive"))
      (node (ref "P1") (pin "6") (pinfunction "6_6") (pintype "passive"))
      (node (ref "P2") (pin "5") (pinfunction "5_5") (pintype "passive"))
      (node (ref "P2") (pin "6") (pinfunction "6_6") (pintype "passive"))
      (node (ref "R6") (pin "2") (pinfunction "2_2") (pintype "passive"))
      (node (ref "R7") (pin "2") (pinfunction "2_2") (pintype "passive"))
      (node (ref "U1") (pin "13") (pinfunction "~{OE}_13") (pintype "input"))
      (node (ref "U1") (pin "8") (pinfunction "GND_8") (pintype "power_in"))
      (node (ref "U2") (pin "13") (pinfunction "~{OE}_13") (pintype "input"))
      (node (ref "U2") (pin "8") (pinfunction "GND_8") (pintype "power_in"))
      (node (ref "U3") (pin "107") (pinfunction "VSS_107") (pintype "power_in"))
      (node (ref "U3") (pin "120") (pinfunction "VSS_120") (pintype "power_in"))
      (node (ref "U3") (pin "130") (pinfunction "VSS_130") (pintype "power_in"))
      (node (ref "U3") (pin "16") (pinfunction "VSS_16") (pintype "power_in"))
      (node (ref "U3") (pin "31") (pinfunction "VSSA_31") (pintype "power_in"))
      (node (ref "U3") (pin "38") (pinfunction "VSS_38") (pintype "power_in"))
      (node (ref "U3") (pin "51") (pinfunction "VSS_51") (pintype "power_in"))
      (node (ref "U3") (pin "61") (pinfunction "VSS_61") (pintype "power_in"))
      (node (ref "U3") (pin "83") (pinfunction "VSS_83") (pintype "power_in"))
      (node (ref "U3") (pin "94") (pinfunction "VSS_94") (pintype "power_in"))
      (node (ref "U4") (pin "4") (pinfunction "VSS_4") (pintype "power_in"))
      (node (ref "U5") (pin "13") (pinfunction "~{OE}_13") (pintype "input"))
      (node (ref "U5") (pin "8") (pinfunction "GND_8") (pintype "power_in"))
    )
    (net (code "115") (name "Net-(*1-TP)") (class "Default")
      (node (ref "*1") (pin "1") (pinfunction "TP_1") (pintype "passive"))
      (node (ref "J4") (pin "1") (pinfunction "VBUS_1") (pintype "power_in"))
    )
    (net (code "116") (name "Net-(*6-TP)") (class "Default")
      (node (ref "*6") (pin "1") (pinfunction "TP_1") (pintype "passive"))
      (node (ref "RN5") (pin "6") (pinfunction "6_6") (pintype "passive"))
    )
    (net (code "117") (name "Net-(*7-TP)") (class "Default")
      (node (ref "*7") (pin "1") (pinfunction "TP_1") (pintype "passive"))
      (node (ref "MD1") (pin "25") (pinfunction "IO0_25") (pintype "bidirectional"))
    )
    (net (code "118") (name "Net-(MD1-EN)") (class "Default")
      (node (ref "MD1") (pin "3") (pinfunction "EN_3") (pintype "input"))
      (node (ref "R2") (pin "1") (pinfunction "1_1") (pintype "passive"))
    )
    (net (code "119") (name "Net-(U1-QA)") (class "Default")
      (node (ref "RN1") (pin "4") (pinfunction "4_4") (pintype "passive"))
      (node (ref "U1") (pin "15") (pinfunction "QA_15") (pintype "output"))
    )
    (net (code "120") (name "Net-(U1-QB)") (class "Default")
      (node (ref "RN1") (pin "3") (pinfunction "3_3") (pintype "passive"))
      (node (ref "U1") (pin "1") (pinfunction "QB_1") (pintype "output"))
    )
    (net (code "121") (name "Net-(U1-QC)") (class "Default")
      (node (ref "RN1") (pin "2") (pinfunction "2_2") (pintype "passive"))
      (node (ref "U1") (pin "2") (pinfunction "QC_2") (pintype "output"))
    )
    (net (code "122") (name "Net-(U1-QD)") (class "Default")
      (node (ref "RN1") (pin "1") (pinfunction "1_1") (pintype "passive"))
      (node (ref "U1") (pin "3") (pinfunction "QD_3") (pintype "output"))
    )
    (net (code "123") (name "Net-(U1-QE)") (class "Default")
      (node (ref "RN2") (pin "4") (pinfunction "4_4") (pintype "passive"))
      (node (ref "U1") (pin "4") (pinfunction "QE_4") (pintype "output"))
    )
    (net (code "124") (name "Net-(U1-QF)") (class "Default")
      (node (ref "RN2") (pin "3") (pinfunction "3_3") (pintype "passive"))
      (node (ref "U1") (pin "5") (pinfunction "QF_5") (pintype "output"))
    )
    (net (code "125") (name "Net-(U1-QG)") (class "Default")
      (node (ref "RN2") (pin "2") (pinfunction "2_2") (pintype "passive"))
      (node (ref "U1") (pin "6") (pinfunction "QG_6") (pintype "output"))
    )
    (net (code "126") (name "Net-(U1-QH')") (class "Default")
      (node (ref "U1") (pin "9") (pinfunction "QH'_9") (pintype "output"))
      (node (ref "U2") (pin "14") (pinfunction "SER_14") (pintype "input"))
    )
    (net (code "127") (name "Net-(U1-QH)") (class "Default")
      (node (ref "RN2") (pin "1") (pinfunction "1_1") (pintype "passive"))
      (node (ref "U1") (pin "7") (pinfunction "QH_7") (pintype "output"))
    )
    (net (code "128") (name "Net-(U2-QA)") (class "Default")
      (node (ref "RN3") (pin "4") (pinfunction "4_4") (pintype "passive"))
      (node (ref "U2") (pin "15") (pinfunction "QA_15") (pintype "output"))
    )
    (net (code "129") (name "Net-(U2-QB)") (class "Default")
      (node (ref "RN3") (pin "3") (pinfunction "3_3") (pintype "passive"))
      (node (ref "U2") (pin "1") (pinfunction "QB_1") (pintype "output"))
    )
    (net (code "130") (name "Net-(U2-QC)") (class "Default")
      (node (ref "RN3") (pin "2") (pinfunction "2_2") (pintype "passive"))
      (node (ref "U2") (pin "2") (pinfunction "QC_2") (pintype "output"))
    )
    (net (code "131") (name "Net-(U2-QD)") (class "Default")
      (node (ref "RN3") (pin "1") (pinfunction "1_1") (pintype "passive"))
      (node (ref "U2") (pin "3") (pinfunction "QD_3") (pintype "output"))
    )
    (net (code "132") (name "Net-(U2-QE)") (class "Default")
      (node (ref "RN4") (pin "4") (pinfunction "4_4") (pintype "passive"))
      (node (ref "U2") (pin "4") (pinfunction "QE_4") (pintype "output"))
    )
    (net (code "133") (name "Net-(U2-QF)") (class "Default")
      (node (ref "RN4") (pin "3") (pinfunction "3_3") (pintype "passive"))
      (node (ref "U2") (pin "5") (pinfunction "QF_5") (pintype "output"))
    )
    (net (code "134") (name "Net-(U2-QG)") (class "Default")
      (node (ref "RN4") (pin "2") (pinfunction "2_2") (pintype "passive"))
      (node (ref "U2") (pin "6") (pinfunction "QG_6") (pintype "output"))
    )
    (net (code "135") (name "Net-(U2-QH')") (class "Default")
      (node (ref "U2") (pin "9") (pinfunction "QH'_9") (pintype "output"))
      (node (ref "U5") (pin "14") (pinfunction "SER_14") (pintype "input"))
    )
    (net (code "136") (name "Net-(U2-QH)") (class "Default")
      (node (ref "RN4") (pin "1") (pinfunction "1_1") (pintype "passive"))
      (node (ref "U2") (pin "7") (pinfunction "QH_7") (pintype "output"))
    )
    (net (code "137") (name "Net-(U3A-BOOT0)") (class "Default")
      (node (ref "R7") (pin "1") (pinfunction "1_1") (pintype "passive"))
      (node (ref "U3") (pin "138") (pinfunction "BOOT0_138") (pintype "input"))
    )
    (net (code "138") (name "Net-(U3A-PDR_ON)") (class "Default")
      (node (ref "R6") (pin "1") (pinfunction "1_1") (pintype "passive"))
      (node (ref "U3") (pin "143") (pinfunction "PDR_ON_143") (pintype "input"))
    )
    (net (code "139") (name "Net-(U3A-VREF+)") (class "Default")
      (node (ref "R3") (pin "1") (pinfunction "1_1") (pintype "passive"))
      (node (ref "U3") (pin "32") (pinfunction "VREF+_32") (pintype "power_in"))
    )
    (net (code "140") (name "Net-(U3D-PH0)") (class "Default")
      (node (ref "C9") (pin "1") (pinfunction "1_1") (pintype "passive"))
      (node (ref "U3") (pin "23") (pinfunction "PH0_23") (pintype "bidirectional"))
      (node (ref "Y1") (pin "2") (pinfunction "2_2") (pintype "passive"))
    )
    (net (code "141") (name "Net-(U3D-PH1)") (class "Default")
      (node (ref "C8") (pin "1") (pinfunction "1_1") (pintype "passive"))
      (node (ref "U3") (pin "24") (pinfunction "PH1_24") (pintype "bidirectional"))
      (node (ref "Y1") (pin "1") (pinfunction "1_1") (pintype "passive"))
    )
    (net (code "142") (name "Net-(U4-~{HOLD})") (class "Default")
      (node (ref "P2") (pin "4") (pinfunction "4_4") (pintype "passive"))
      (node (ref "U4") (pin "7") (pinfunction "~{HOLD}_7") (pintype "input"))
    )
    (net (code "143") (name "Net-(U4-~{W})") (class "Default")
      (node (ref "P2") (pin "3") (pinfunction "3_3") (pintype "passive"))
      (node (ref "U4") (pin "3") (pinfunction "~{W}_3") (pintype "input"))
    )
    (net (code "144") (name "Net-(U5-QA)") (class "Default")
      (node (ref "RN5") (pin "4") (pinfunction "4_4") (pintype "passive"))
      (node (ref "U5") (pin "15") (pinfunction "QA_15") (pintype "output"))
    )
    (net (code "145") (name "Net-(U5-QB)") (class "Default")
      (node (ref "RN5") (pin "3") (pinfunction "3_3") (pintype "passive"))
      (node (ref "U5") (pin "1") (pinfunction "QB_1") (pintype "output"))
    )
    (net (code "146") (name "Net-(U5-QC)") (class "Default")
      (node (ref "RN5") (pin "2") (pinfunction "2_2") (pintype "passive"))
      (node (ref "U5") (pin "2") (pinfunction "QC_2") (pintype "output"))
    )
    (net (code "147") (name "Net-(U5-QD)") (class "Default")
      (node (ref "RN5") (pin "1") (pinfunction "1_1") (pintype "passive"))
      (node (ref "U5") (pin "3") (pinfunction "QD_3") (pintype "output"))
    )
    (net (code "148") (name "Net-(U5-QE)") (class "Default")
      (node (ref "RN6") (pin "4") (pinfunction "4_4") (pintype "passive"))
      (node (ref "U5") (pin "4") (pinfunction "QE_4") (pintype "output"))
    )
    (net (code "149") (name "Net-(U5-QF)") (class "Default")
      (node (ref "RN6") (pin "3") (pinfunction "3_3") (pintype "passive"))
      (node (ref "U5") (pin "5") (pinfunction "QF_5") (pintype "output"))
    )
    (net (code "150") (name "Net-(U5-QG)") (class "Default")
      (node (ref "RN6") (pin "2") (pinfunction "2_2") (pintype "passive"))
      (node (ref "U5") (pin "6") (pinfunction "QG_6") (pintype "output"))
    )
    (net (code "151") (name "Net-(U5-QH)") (class "Default")
      (node (ref "RN6") (pin "1") (pinfunction "1_1") (pintype "passive"))
      (node (ref "U5") (pin "7") (pinfunction "QH_7") (pintype "output"))
    )
    (net (code "152") (name "unconnected-(J4-ID-Pad4)") (class "Default")
      (node (ref "J4") (pin "4") (pinfunction "ID_4") (pintype "passive+no_connect"))
    )
    (net (code "153") (name "unconnected-(MD1-CLK-Pad20)") (class "Default")
      (node (ref "MD1") (pin "20") (pinfunction "CLK_20") (pintype "bidirectional+no_connect"))
    )
    (net (code "154") (name "unconnected-(MD1-CMD-Pad19)") (class "Default")
      (node (ref "MD1") (pin "19") (pinfunction "CMD_19") (pintype "bidirectional+no_connect"))
    )
    (net (code "155") (name "unconnected-(MD1-IO2-Pad24)") (class "Default")
      (node (ref "MD1") (pin "24") (pinfunction "IO2_24") (pintype "bidirectional+no_connect"))
    )
    (net (code "156") (name "unconnected-(MD1-IO4-Pad26)") (class "Default")
      (node (ref "MD1") (pin "26") (pinfunction "IO4_26") (pintype "bidirectional+no_connect"))
    )
    (net (code "157") (name "unconnected-(MD1-IO5-Pad29)") (class "Default")
      (node (ref "MD1") (pin "29") (pinfunction "IO5_29") (pintype "bidirectional+no_connect"))
    )
    (net (code "158") (name "unconnected-(MD1-IO12-Pad14)") (class "Default")
      (node (ref "MD1") (pin "14") (pinfunction "IO12_14") (pintype "bidirectional+no_connect"))
    )
    (net (code "159") (name "unconnected-(MD1-IO13-Pad16)") (class "Default")
      (node (ref "MD1") (pin "16") (pinfunction "IO13_16") (pintype "bidirectional+no_connect"))
    )
    (net (code "160") (name "unconnected-(MD1-IO14-Pad13)") (class "Default")
      (node (ref "MD1") (pin "13") (pinfunction "IO14_13") (pintype "bidirectional+no_connect"))
    )
    (net (code "161") (name "unconnected-(MD1-IO15-Pad23)") (class "Default")
      (node (ref "MD1") (pin "23") (pinfunction "IO15_23") (pintype "bidirectional+no_connect"))
    )
    (net (code "162") (name "unconnected-(MD1-IO16-Pad27)") (class "Default")
      (node (ref "MD1") (pin "27") (pinfunction "IO16_27") (pintype "bidirectional+no_connect"))
    )
    (net (code "163") (name "unconnected-(MD1-IO17-Pad28)") (class "Default")
      (node (ref "MD1") (pin "28") (pinfunction "IO17_28") (pintype "bidirectional+no_connect"))
    )
    (net (code "164") (name "unconnected-(MD1-IO18-Pad30)") (class "Default")
      (node (ref "MD1") (pin "30") (pinfunction "IO18_30") (pintype "bidirectional+no_connect"))
    )
    (net (code "165") (name "unconnected-(MD1-IO19-Pad31)") (class "Default")
      (node (ref "MD1") (pin "31") (pinfunction "IO19_31") (pintype "bidirectional+no_connect"))
    )
    (net (code "166") (name "unconnected-(MD1-IO21-Pad33)") (class "Default")
      (node (ref "MD1") (pin "33") (pinfunction "IO21_33") (pintype "bidirectional+no_connect"))
    )
    (net (code "167") (name "unconnected-(MD1-IO22-Pad36)") (class "Default")
      (node (ref "MD1") (pin "36") (pinfunction "IO22_36") (pintype "bidirectional+no_connect"))
    )
    (net (code "168") (name "unconnected-(MD1-IO23-Pad37)") (class "Default")
      (node (ref "MD1") (pin "37") (pinfunction "IO23_37") (pintype "bidirectional+no_connect"))
    )
    (net (code "169") (name "unconnected-(MD1-IO25-Pad10)") (class "Default")
      (node (ref "MD1") (pin "10") (pinfunction "IO25_10") (pintype "bidirectional+no_connect"))
    )
    (net (code "170") (name "unconnected-(MD1-IO26-Pad11)") (class "Default")
      (node (ref "MD1") (pin "11") (pinfunction "IO26_11") (pintype "bidirectional+no_connect"))
    )
    (net (code "171") (name "unconnected-(MD1-IO27-Pad12)") (class "Default")
      (node (ref "MD1") (pin "12") (pinfunction "IO27_12") (pintype "bidirectional+no_connect"))
    )
    (net (code "172") (name "unconnected-(MD1-IO32-Pad8)") (class "Default")
      (node (ref "MD1") (pin "8") (pinfunction "IO32_8") (pintype "bidirectional+no_connect"))
    )
    (net (code "173") (name "unconnected-(MD1-IO33-Pad9)") (class "Default")
      (node (ref "MD1") (pin "9") (pinfunction "IO33_9") (pintype "bidirectional+no_connect"))
    )
    (net (code "174") (name "unconnected-(MD1-IO34-Pad6)") (class "Default")
      (node (ref "MD1") (pin "6") (pinfunction "IO34_6") (pintype "bidirectional+no_connect"))
    )
    (net (code "175") (name "unconnected-(MD1-IO35-Pad7)") (class "Default")
      (node (ref "MD1") (pin "7") (pinfunction "IO35_7") (pintype "bidirectional+no_connect"))
    )
    (net (code "176") (name "unconnected-(MD1-NC-Pad32)") (class "Default")
      (node (ref "MD1") (pin "32") (pinfunction "NC_32") (pintype "passive+no_connect"))
    )
    (net (code "177") (name "unconnected-(MD1-SD0-Pad21)") (class "Default")
      (node (ref "MD1") (pin "21") (pinfunction "SD0_21") (pintype "bidirectional+no_connect"))
    )
    (net (code "178") (name "unconnected-(MD1-SD1-Pad22)") (class "Default")
      (node (ref "MD1") (pin "22") (pinfunction "SD1_22") (pintype "bidirectional+no_connect"))
    )
    (net (code "179") (name "unconnected-(MD1-SD2-Pad17)") (class "Default")
      (node (ref "MD1") (pin "17") (pinfunction "SD2_17") (pintype "bidirectional+no_connect"))
    )
    (net (code "180") (name "unconnected-(MD1-SD3-Pad18)") (class "Default")
      (node (ref "MD1") (pin "18") (pinfunction "SD3_18") (pintype "bidirectional+no_connect"))
    )
    (net (code "181") (name "unconnected-(MD1-SENSOR_VN-Pad5)") (class "Default")
      (node (ref "MD1") (pin "5") (pinfunction "SENSOR_VN_5") (pintype "bidirectional+no_connect"))
    )
    (net (code "182") (name "unconnected-(MD1-SENSOR_VP-Pad4)") (class "Default")
      (node (ref "MD1") (pin "4") (pinfunction "SENSOR_VP_4") (pintype "bidirectional+no_connect"))
    )
    (net (code "183") (name "unconnected-(RN5-Pad5)") (class "Default")
      (node (ref "RN5") (pin "5") (pinfunction "5_5") (pintype "passive+no_connect"))
    )
    (net (code "184") (name "unconnected-(RN6-Pad5)") (class "Default")
      (node (ref "RN6") (pin "5") (pinfunction "5_5") (pintype "passive+no_connect"))
    )
    (net (code "185") (name "unconnected-(RN6-Pad6)") (class "Default")
      (node (ref "RN6") (pin "6") (pinfunction "6_6") (pintype "passive+no_connect"))
    )
    (net (code "186") (name "unconnected-(RN6-Pad7)") (class "Default")
      (node (ref "RN6") (pin "7") (pinfunction "7_7") (pintype "passive+no_connect"))
    )
    (net (code "187") (name "unconnected-(RN6-Pad8)") (class "Default")
      (node (ref "RN6") (pin "8") (pinfunction "8_8") (pintype "passive+no_connect"))
    )
    (net (code "188") (name "unconnected-(U3A-PA15-Pad110)") (class "Default")
      (node (ref "U3") (pin "110") (pinfunction "PA15_110") (pintype "bidirectional+no_connect"))
    )
    (net (code "189") (name "unconnected-(U3A-VCAP_1-Pad71)") (class "Default")
      (node (ref "U3") (pin "71") (pinfunction "VCAP_1_71") (pintype "power_in+no_connect"))
    )
    (net (code "190") (name "unconnected-(U3A-VCAP_2-Pad106)") (class "Default")
      (node (ref "U3") (pin "106") (pinfunction "VCAP_2_106") (pintype "power_in+no_connect"))
    )
    (net (code "191") (name "unconnected-(U3B-PB4-Pad134)") (class "Default")
      (node (ref "U3") (pin "134") (pinfunction "PB4_134") (pintype "bidirectional+no_connect"))
    )
    (net (code "192") (name "unconnected-(U3B-PB5-Pad135)") (class "Default")
      (node (ref "U3") (pin "135") (pinfunction "PB5_135") (pintype "bidirectional+no_connect"))
    )
    (net (code "193") (name "unconnected-(U3B-PB12-Pad73)") (class "Default")
      (node (ref "U3") (pin "73") (pinfunction "PB12_73") (pintype "bidirectional+no_connect"))
    )
    (net (code "194") (name "unconnected-(U3B-PC2-Pad28)") (class "Default")
      (node (ref "U3") (pin "28") (pinfunction "PC2_28") (pintype "bidirectional+no_connect"))
    )
    (net (code "195") (name "unconnected-(U3B-PC5-Pad45)") (class "Default")
      (node (ref "U3") (pin "45") (pinfunction "PC5_45") (pintype "bidirectional+no_connect"))
    )
    (net (code "196") (name "unconnected-(U3B-PC15-Pad9)") (class "Default")
      (node (ref "U3") (pin "9") (pinfunction "PC15_9") (pintype "bidirectional+no_connect"))
    )
    (net (code "197") (name "unconnected-(U3C-PD2-Pad116)") (class "Default")
      (node (ref "U3") (pin "116") (pinfunction "PD2_116") (pintype "bidirectional+no_connect"))
    )
    (net (code "198") (name "unconnected-(U3C-PD11-Pad80)") (class "Default")
      (node (ref "U3") (pin "80") (pinfunction "PD11_80") (pintype "bidirectional+no_connect"))
    )
    (net (code "199") (name "unconnected-(U3C-PE2-Pad1)") (class "Default")
      (node (ref "U3") (pin "1") (pinfunction "PE2_1") (pintype "bidirectional+no_connect"))
    )
    (net (code "200") (name "unconnected-(U3C-PE3-Pad2)") (class "Default")
      (node (ref "U3") (pin "2") (pinfunction "PE3_2") (pintype "bidirectional+no_connect"))
    )
    (net (code "201") (name "unconnected-(U3D-PF6-Pad18)") (class "Default")
      (node (ref "U3") (pin "18") (pinfunction "PF6_18") (pintype "bidirectional+no_connect"))
    )
    (net (code "202") (name "unconnected-(U3D-PF7-Pad19)") (class "Default")
      (node (ref "U3") (pin "19") (pinfunction "PF7_19") (pintype "bidirectional+no_connect"))
    )
    (net (code "203") (name "unconnected-(U3D-PF8-Pad20)") (class "Default")
      (node (ref "U3") (pin "20") (pinfunction "PF8_20") (pintype "bidirectional+no_connect"))
    )
    (net (code "204") (name "unconnected-(U3D-PF9-Pad21)") (class "Default")
      (node (ref "U3") (pin "21") (pinfunction "PF9_21") (pintype "bidirectional+no_connect"))
    )
    (net (code "205") (name "unconnected-(U3D-PG2-Pad87)") (class "Default")
      (node (ref "U3") (pin "87") (pinfunction "PG2_87") (pintype "bidirectional+no_connect"))
    )
    (net (code "206") (name "unconnected-(U3D-PG9-Pad124)") (class "Default")
      (node (ref "U3") (pin "124") (pinfunction "PG9_124") (pintype "bidirectional+no_connect"))
    )
    (net (code "207") (name "unconnected-(U3D-PG10-Pad125)") (class "Default")
      (node (ref "U3") (pin "125") (pinfunction "PG10_125") (pintype "bidirectional+no_connect"))
    )
    (net (code "208") (name "unconnected-(U3D-PG14-Pad129)") (class "Default")
      (node (ref "U3") (pin "129") (pinfunction "PG14_129") (pintype "bidirectional+no_connect"))
    )
    (net (code "209") (name "unconnected-(U5-QH'-Pad9)") (class "Default")
      (node (ref "U5") (pin "9") (pinfunction "QH'_9") (pintype "output+no_connect"))
    )
  )
)
